# 2_viper_eagle_modern_matrix.net
KiCad netlist of a schematic drawn in Altium Designer
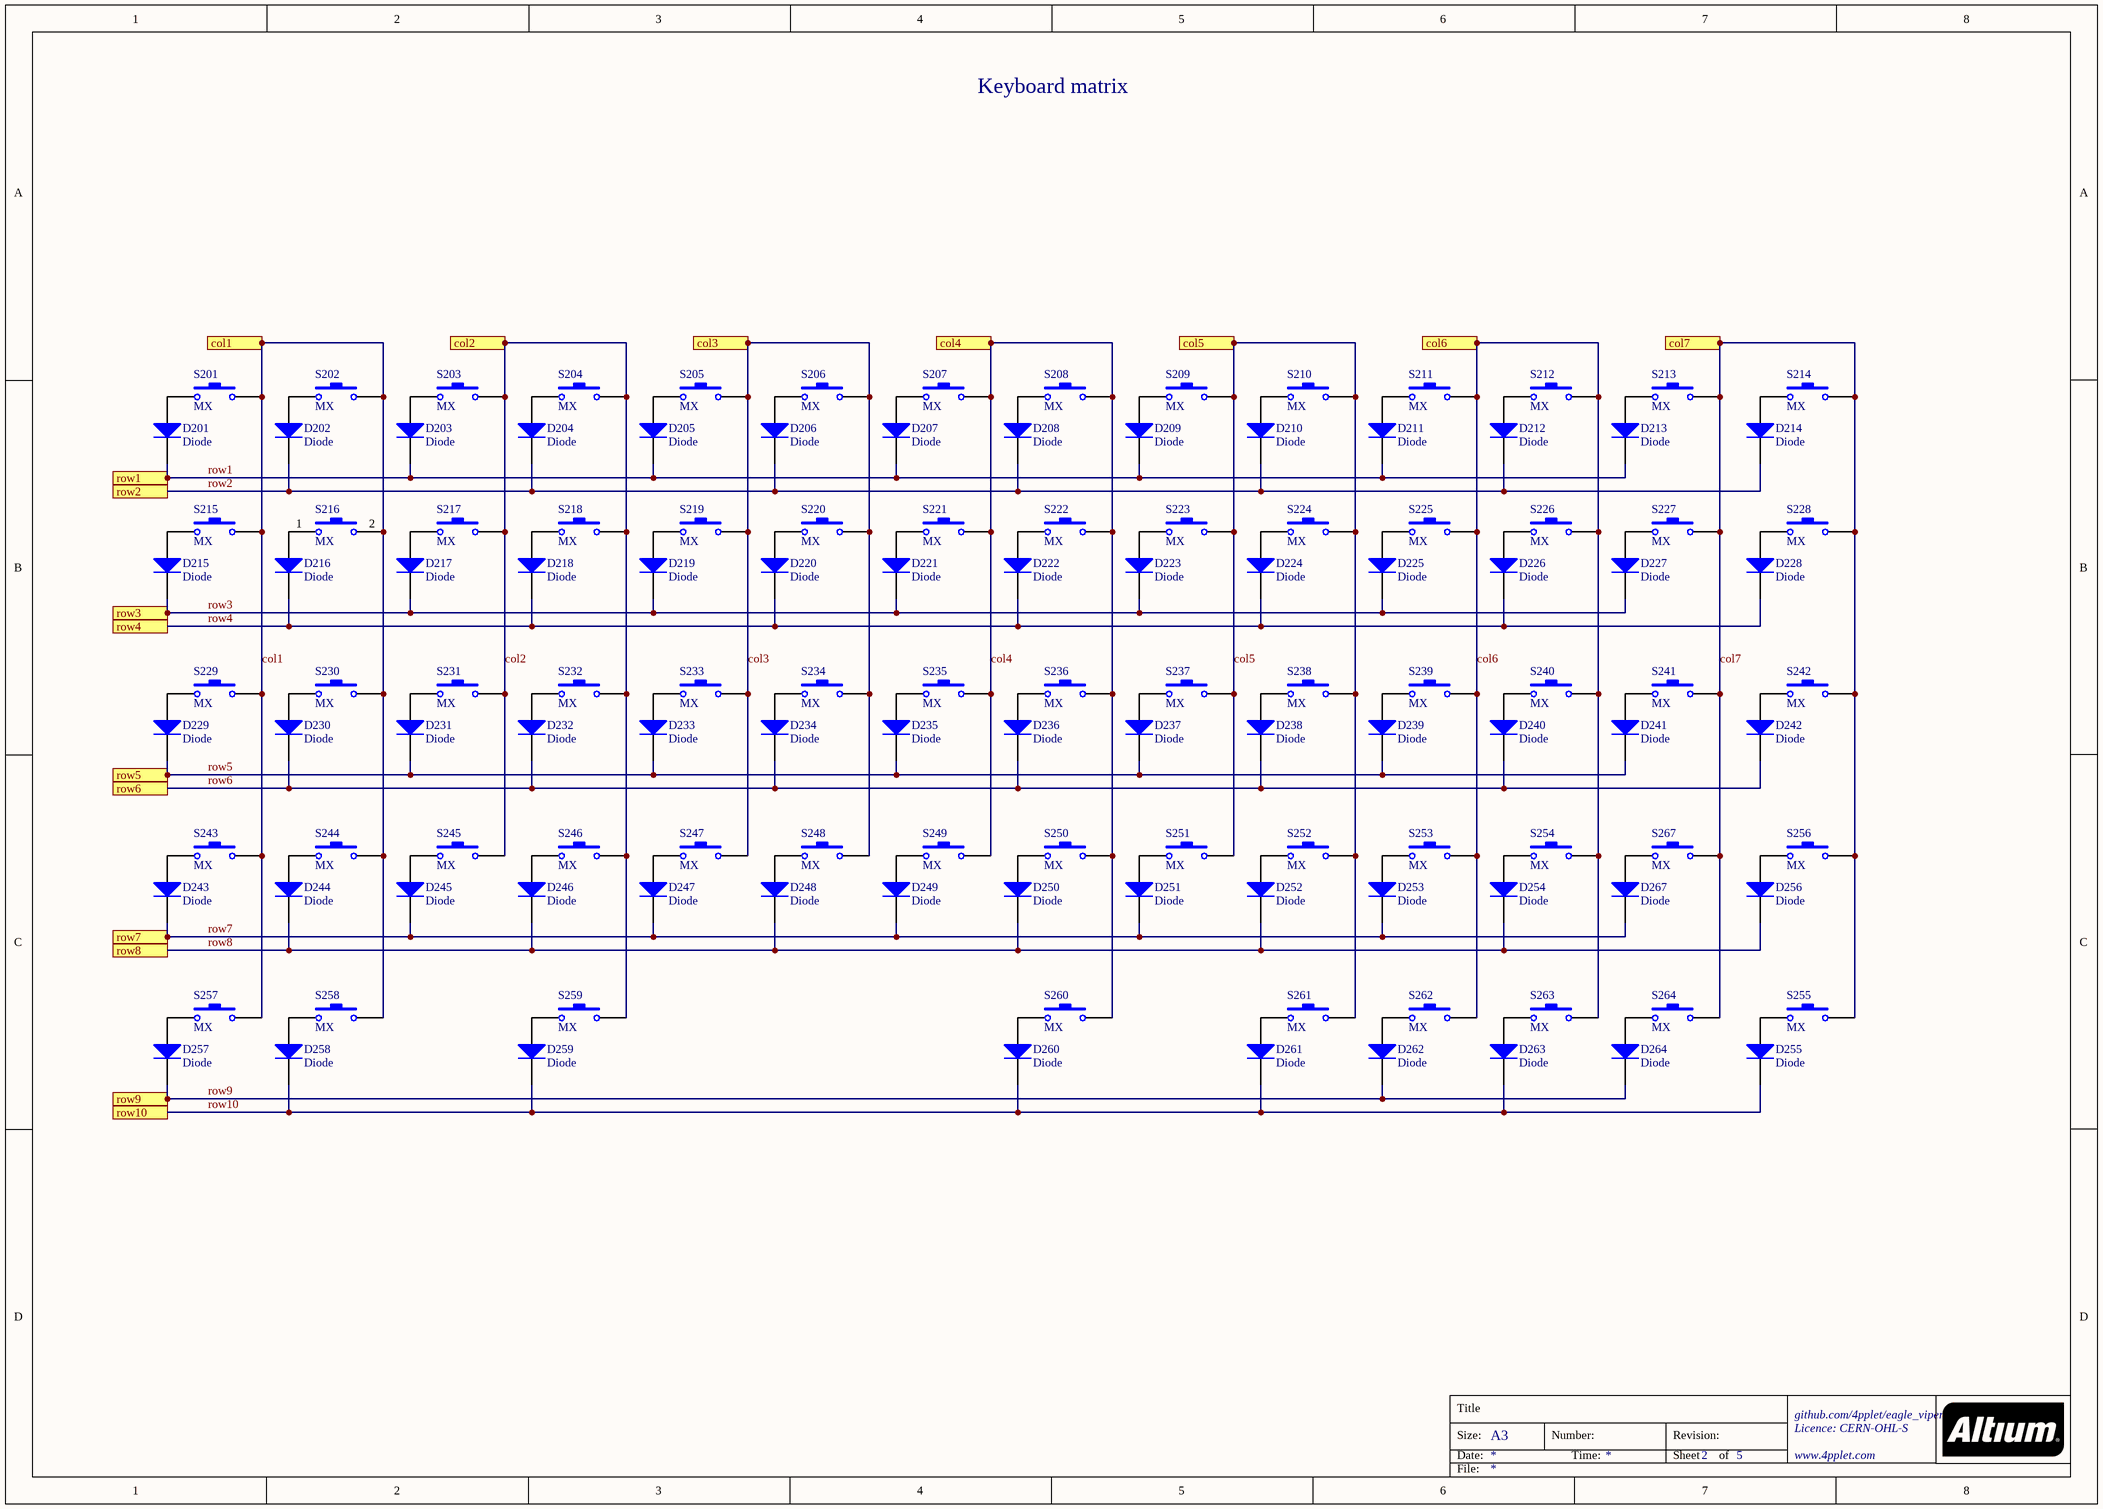
[diagram p0: 2_viper_eagle_modern_matrix.SchDoc]

(export (version "E")
  (design (tool "Eeschema 10.0.6"))
  (components
    (comp (ref "D201")
      (value "Diode")
      (footprint "SOD-123")
      (description "Default Diode")
      (fields (field (name "LCSC PART #") "C81598") (field (name "MRF.PART") "1N4148W"))
      (libsource (lib "Miscellaneous Devices") (part "Diode"))
    )
    (comp (ref "D202")
      (value "Diode")
      (footprint "SOD-123")
      (description "Default Diode")
      (fields (field (name "LCSC PART #") "C81598") (field (name "MRF.PART") "1N4148W"))
      (libsource (lib "Miscellaneous Devices") (part "Diode"))
    )
    (comp (ref "D203")
      (value "Diode")
      (footprint "SOD-123")
      (description "Default Diode")
      (fields (field (name "LCSC PART #") "C81598") (field (name "MRF.PART") "1N4148W"))
      (libsource (lib "Miscellaneous Devices") (part "Diode"))
    )
    (comp (ref "D204")
      (value "Diode")
      (footprint "SOD-123")
      (description "Default Diode")
      (fields (field (name "LCSC PART #") "C81598") (field (name "MRF.PART") "1N4148W"))
      (libsource (lib "Miscellaneous Devices") (part "Diode"))
    )
    (comp (ref "D205")
      (value "Diode")
      (footprint "SOD-123")
      (description "Default Diode")
      (fields (field (name "LCSC PART #") "C81598") (field (name "MRF.PART") "1N4148W"))
      (libsource (lib "Miscellaneous Devices") (part "Diode"))
    )
    (comp (ref "D206")
      (value "Diode")
      (footprint "SOD-123")
      (description "Default Diode")
      (fields (field (name "LCSC PART #") "C81598") (field (name "MRF.PART") "1N4148W"))
      (libsource (lib "Miscellaneous Devices") (part "Diode"))
    )
    (comp (ref "D207")
      (value "Diode")
      (footprint "SOD-123")
      (description "Default Diode")
      (fields (field (name "LCSC PART #") "C81598") (field (name "MRF.PART") "1N4148W"))
      (libsource (lib "Miscellaneous Devices") (part "Diode"))
    )
    (comp (ref "D208")
      (value "Diode")
      (footprint "SOD-123")
      (description "Default Diode")
      (fields (field (name "LCSC PART #") "C81598") (field (name "MRF.PART") "1N4148W"))
      (libsource (lib "Miscellaneous Devices") (part "Diode"))
    )
    (comp (ref "D209")
      (value "Diode")
      (footprint "SOD-123")
      (description "Default Diode")
      (fields (field (name "LCSC PART #") "C81598") (field (name "MRF.PART") "1N4148W"))
      (libsource (lib "Miscellaneous Devices") (part "Diode"))
    )
    (comp (ref "D210")
      (value "Diode")
      (footprint "SOD-123")
      (description "Default Diode")
      (fields (field (name "LCSC PART #") "C81598") (field (name "MRF.PART") "1N4148W"))
      (libsource (lib "Miscellaneous Devices") (part "Diode"))
    )
    (comp (ref "D211")
      (value "Diode")
      (footprint "SOD-123")
      (description "Default Diode")
      (fields (field (name "LCSC PART #") "C81598") (field (name "MRF.PART") "1N4148W"))
      (libsource (lib "Miscellaneous Devices") (part "Diode"))
    )
    (comp (ref "D212")
      (value "Diode")
      (footprint "SOD-123")
      (description "Default Diode")
      (fields (field (name "LCSC PART #") "C81598") (field (name "MRF.PART") "1N4148W"))
      (libsource (lib "Miscellaneous Devices") (part "Diode"))
    )
    (comp (ref "D213")
      (value "Diode")
      (footprint "SOD-123")
      (description "Default Diode")
      (fields (field (name "LCSC PART #") "C81598") (field (name "MRF.PART") "1N4148W"))
      (libsource (lib "Miscellaneous Devices") (part "Diode"))
    )
    (comp (ref "D214")
      (value "Diode")
      (footprint "SOD-123")
      (description "Default Diode")
      (fields (field (name "LCSC PART #") "C81598") (field (name "MRF.PART") "1N4148W"))
      (libsource (lib "Miscellaneous Devices") (part "Diode"))
    )
    (comp (ref "D215")
      (value "Diode")
      (footprint "SOD-123")
      (description "Default Diode")
      (fields (field (name "LCSC PART #") "C81598") (field (name "MRF.PART") "1N4148W"))
      (libsource (lib "Miscellaneous Devices") (part "Diode"))
    )
    (comp (ref "D216")
      (value "Diode")
      (footprint "SOD-123")
      (description "Default Diode")
      (fields (field (name "LCSC PART #") "C81598") (field (name "MRF.PART") "1N4148W"))
      (libsource (lib "Miscellaneous Devices") (part "Diode"))
    )
    (comp (ref "D217")
      (value "Diode")
      (footprint "SOD-123")
      (description "Default Diode")
      (fields (field (name "LCSC PART #") "C81598") (field (name "MRF.PART") "1N4148W"))
      (libsource (lib "Miscellaneous Devices") (part "Diode"))
    )
    (comp (ref "D218")
      (value "Diode")
      (footprint "SOD-123")
      (description "Default Diode")
      (fields (field (name "LCSC PART #") "C81598") (field (name "MRF.PART") "1N4148W"))
      (libsource (lib "Miscellaneous Devices") (part "Diode"))
    )
    (comp (ref "D219")
      (value "Diode")
      (footprint "SOD-123")
      (description "Default Diode")
      (fields (field (name "LCSC PART #") "C81598") (field (name "MRF.PART") "1N4148W"))
      (libsource (lib "Miscellaneous Devices") (part "Diode"))
    )
    (comp (ref "D220")
      (value "Diode")
      (footprint "SOD-123")
      (description "Default Diode")
      (fields (field (name "LCSC PART #") "C81598") (field (name "MRF.PART") "1N4148W"))
      (libsource (lib "Miscellaneous Devices") (part "Diode"))
    )
    (comp (ref "D221")
      (value "Diode")
      (footprint "SOD-123")
      (description "Default Diode")
      (fields (field (name "LCSC PART #") "C81598") (field (name "MRF.PART") "1N4148W"))
      (libsource (lib "Miscellaneous Devices") (part "Diode"))
    )
    (comp (ref "D222")
      (value "Diode")
      (footprint "SOD-123")
      (description "Default Diode")
      (fields (field (name "LCSC PART #") "C81598") (field (name "MRF.PART") "1N4148W"))
      (libsource (lib "Miscellaneous Devices") (part "Diode"))
    )
    (comp (ref "D223")
      (value "Diode")
      (footprint "SOD-123")
      (description "Default Diode")
      (fields (field (name "LCSC PART #") "C81598") (field (name "MRF.PART") "1N4148W"))
      (libsource (lib "Miscellaneous Devices") (part "Diode"))
    )
    (comp (ref "D224")
      (value "Diode")
      (footprint "SOD-123")
      (description "Default Diode")
      (fields (field (name "LCSC PART #") "C81598") (field (name "MRF.PART") "1N4148W"))
      (libsource (lib "Miscellaneous Devices") (part "Diode"))
    )
    (comp (ref "D225")
      (value "Diode")
      (footprint "SOD-123")
      (description "Default Diode")
      (fields (field (name "LCSC PART #") "C81598") (field (name "MRF.PART") "1N4148W"))
      (libsource (lib "Miscellaneous Devices") (part "Diode"))
    )
    (comp (ref "D226")
      (value "Diode")
      (footprint "SOD-123")
      (description "Default Diode")
      (fields (field (name "LCSC PART #") "C81598") (field (name "MRF.PART") "1N4148W"))
      (libsource (lib "Miscellaneous Devices") (part "Diode"))
    )
    (comp (ref "D227")
      (value "Diode")
      (footprint "SOD-123")
      (description "Default Diode")
      (fields (field (name "LCSC PART #") "C81598") (field (name "MRF.PART") "1N4148W"))
      (libsource (lib "Miscellaneous Devices") (part "Diode"))
    )
    (comp (ref "D228")
      (value "Diode")
      (footprint "SOD-123")
      (description "Default Diode")
      (fields (field (name "LCSC PART #") "C81598") (field (name "MRF.PART") "1N4148W"))
      (libsource (lib "Miscellaneous Devices") (part "Diode"))
    )
    (comp (ref "D229")
      (value "Diode")
      (footprint "SOD-123")
      (description "Default Diode")
      (fields (field (name "LCSC PART #") "C81598") (field (name "MRF.PART") "1N4148W"))
      (libsource (lib "Miscellaneous Devices") (part "Diode"))
    )
    (comp (ref "D230")
      (value "Diode")
      (footprint "SOD-123")
      (description "Default Diode")
      (fields (field (name "LCSC PART #") "C81598") (field (name "MRF.PART") "1N4148W"))
      (libsource (lib "Miscellaneous Devices") (part "Diode"))
    )
    (comp (ref "D231")
      (value "Diode")
      (footprint "SOD-123")
      (description "Default Diode")
      (fields (field (name "LCSC PART #") "C81598") (field (name "MRF.PART") "1N4148W"))
      (libsource (lib "Miscellaneous Devices") (part "Diode"))
    )
    (comp (ref "D232")
      (value "Diode")
      (footprint "SOD-123")
      (description "Default Diode")
      (fields (field (name "LCSC PART #") "C81598") (field (name "MRF.PART") "1N4148W"))
      (libsource (lib "Miscellaneous Devices") (part "Diode"))
    )
    (comp (ref "D233")
      (value "Diode")
      (footprint "SOD-123")
      (description "Default Diode")
      (fields (field (name "LCSC PART #") "C81598") (field (name "MRF.PART") "1N4148W"))
      (libsource (lib "Miscellaneous Devices") (part "Diode"))
    )
    (comp (ref "D234")
      (value "Diode")
      (footprint "SOD-123")
      (description "Default Diode")
      (fields (field (name "LCSC PART #") "C81598") (field (name "MRF.PART") "1N4148W"))
      (libsource (lib "Miscellaneous Devices") (part "Diode"))
    )
    (comp (ref "D235")
      (value "Diode")
      (footprint "SOD-123")
      (description "Default Diode")
      (fields (field (name "LCSC PART #") "C81598") (field (name "MRF.PART") "1N4148W"))
      (libsource (lib "Miscellaneous Devices") (part "Diode"))
    )
    (comp (ref "D236")
      (value "Diode")
      (footprint "SOD-123")
      (description "Default Diode")
      (fields (field (name "LCSC PART #") "C81598") (field (name "MRF.PART") "1N4148W"))
      (libsource (lib "Miscellaneous Devices") (part "Diode"))
    )
    (comp (ref "D237")
      (value "Diode")
      (footprint "SOD-123")
      (description "Default Diode")
      (fields (field (name "LCSC PART #") "C81598") (field (name "MRF.PART") "1N4148W"))
      (libsource (lib "Miscellaneous Devices") (part "Diode"))
    )
    (comp (ref "D238")
      (value "Diode")
      (footprint "SOD-123")
      (description "Default Diode")
      (fields (field (name "LCSC PART #") "C81598") (field (name "MRF.PART") "1N4148W"))
      (libsource (lib "Miscellaneous Devices") (part "Diode"))
    )
    (comp (ref "D239")
      (value "Diode")
      (footprint "SOD-123")
      (description "Default Diode")
      (fields (field (name "LCSC PART #") "C81598") (field (name "MRF.PART") "1N4148W"))
      (libsource (lib "Miscellaneous Devices") (part "Diode"))
    )
    (comp (ref "D240")
      (value "Diode")
      (footprint "SOD-123")
      (description "Default Diode")
      (fields (field (name "LCSC PART #") "C81598") (field (name "MRF.PART") "1N4148W"))
      (libsource (lib "Miscellaneous Devices") (part "Diode"))
    )
    (comp (ref "D241")
      (value "Diode")
      (footprint "SOD-123")
      (description "Default Diode")
      (fields (field (name "LCSC PART #") "C81598") (field (name "MRF.PART") "1N4148W"))
      (libsource (lib "Miscellaneous Devices") (part "Diode"))
    )
    (comp (ref "D242")
      (value "Diode")
      (footprint "SOD-123")
      (description "Default Diode")
      (fields (field (name "LCSC PART #") "C81598") (field (name "MRF.PART") "1N4148W"))
      (libsource (lib "Miscellaneous Devices") (part "Diode"))
    )
    (comp (ref "D243")
      (value "Diode")
      (footprint "SOD-123")
      (description "Default Diode")
      (fields (field (name "LCSC PART #") "C81598") (field (name "MRF.PART") "1N4148W"))
      (libsource (lib "Miscellaneous Devices") (part "Diode"))
    )
    (comp (ref "D244")
      (value "Diode")
      (footprint "SOD-123")
      (description "Default Diode")
      (fields (field (name "LCSC PART #") "C81598") (field (name "MRF.PART") "1N4148W"))
      (libsource (lib "Miscellaneous Devices") (part "Diode"))
    )
    (comp (ref "D245")
      (value "Diode")
      (footprint "SOD-123")
      (description "Default Diode")
      (fields (field (name "LCSC PART #") "C81598") (field (name "MRF.PART") "1N4148W"))
      (libsource (lib "Miscellaneous Devices") (part "Diode"))
    )
    (comp (ref "D246")
      (value "Diode")
      (footprint "SOD-123")
      (description "Default Diode")
      (fields (field (name "LCSC PART #") "C81598") (field (name "MRF.PART") "1N4148W"))
      (libsource (lib "Miscellaneous Devices") (part "Diode"))
    )
    (comp (ref "D247")
      (value "Diode")
      (footprint "SOD-123")
      (description "Default Diode")
      (fields (field (name "LCSC PART #") "C81598") (field (name "MRF.PART") "1N4148W"))
      (libsource (lib "Miscellaneous Devices") (part "Diode"))
    )
    (comp (ref "D248")
      (value "Diode")
      (footprint "SOD-123")
      (description "Default Diode")
      (fields (field (name "LCSC PART #") "C81598") (field (name "MRF.PART") "1N4148W"))
      (libsource (lib "Miscellaneous Devices") (part "Diode"))
    )
    (comp (ref "D249")
      (value "Diode")
      (footprint "SOD-123")
      (description "Default Diode")
      (fields (field (name "LCSC PART #") "C81598") (field (name "MRF.PART") "1N4148W"))
      (libsource (lib "Miscellaneous Devices") (part "Diode"))
    )
    (comp (ref "D250")
      (value "Diode")
      (footprint "SOD-123")
      (description "Default Diode")
      (fields (field (name "LCSC PART #") "C81598") (field (name "MRF.PART") "1N4148W"))
      (libsource (lib "Miscellaneous Devices") (part "Diode"))
    )
    (comp (ref "D251")
      (value "Diode")
      (footprint "SOD-123")
      (description "Default Diode")
      (fields (field (name "LCSC PART #") "C81598") (field (name "MRF.PART") "1N4148W"))
      (libsource (lib "Miscellaneous Devices") (part "Diode"))
    )
    (comp (ref "D252")
      (value "Diode")
      (footprint "SOD-123")
      (description "Default Diode")
      (fields (field (name "LCSC PART #") "C81598") (field (name "MRF.PART") "1N4148W"))
      (libsource (lib "Miscellaneous Devices") (part "Diode"))
    )
    (comp (ref "D253")
      (value "Diode")
      (footprint "SOD-123")
      (description "Default Diode")
      (fields (field (name "LCSC PART #") "C81598") (field (name "MRF.PART") "1N4148W"))
      (libsource (lib "Miscellaneous Devices") (part "Diode"))
    )
    (comp (ref "D254")
      (value "Diode")
      (footprint "SOD-123")
      (description "Default Diode")
      (fields (field (name "LCSC PART #") "C81598") (field (name "MRF.PART") "1N4148W"))
      (libsource (lib "Miscellaneous Devices") (part "Diode"))
    )
    (comp (ref "D255")
      (value "Diode")
      (footprint "SOD-123")
      (description "Default Diode")
      (fields (field (name "LCSC PART #") "C81598") (field (name "MRF.PART") "1N4148W"))
      (libsource (lib "Miscellaneous Devices") (part "Diode"))
    )
    (comp (ref "D256")
      (value "Diode")
      (footprint "SOD-123")
      (description "Default Diode")
      (fields (field (name "LCSC PART #") "C81598") (field (name "MRF.PART") "1N4148W"))
      (libsource (lib "Miscellaneous Devices") (part "Diode"))
    )
    (comp (ref "D257")
      (value "Diode")
      (footprint "SOD-123")
      (description "Default Diode")
      (fields (field (name "LCSC PART #") "C81598") (field (name "MRF.PART") "1N4148W"))
      (libsource (lib "Miscellaneous Devices") (part "Diode"))
    )
    (comp (ref "D258")
      (value "Diode")
      (footprint "SOD-123")
      (description "Default Diode")
      (fields (field (name "LCSC PART #") "C81598") (field (name "MRF.PART") "1N4148W"))
      (libsource (lib "Miscellaneous Devices") (part "Diode"))
    )
    (comp (ref "D259")
      (value "Diode")
      (footprint "SOD-123")
      (description "Default Diode")
      (fields (field (name "LCSC PART #") "C81598") (field (name "MRF.PART") "1N4148W"))
      (libsource (lib "Miscellaneous Devices") (part "Diode"))
    )
    (comp (ref "D260")
      (value "Diode")
      (footprint "SOD-123")
      (description "Default Diode")
      (fields (field (name "LCSC PART #") "C81598") (field (name "MRF.PART") "1N4148W"))
      (libsource (lib "Miscellaneous Devices") (part "Diode"))
    )
    (comp (ref "D261")
      (value "Diode")
      (footprint "SOD-123")
      (description "Default Diode")
      (fields (field (name "LCSC PART #") "C81598") (field (name "MRF.PART") "1N4148W"))
      (libsource (lib "Miscellaneous Devices") (part "Diode"))
    )
    (comp (ref "D262")
      (value "Diode")
      (footprint "SOD-123")
      (description "Default Diode")
      (fields (field (name "LCSC PART #") "C81598") (field (name "MRF.PART") "1N4148W"))
      (libsource (lib "Miscellaneous Devices") (part "Diode"))
    )
    (comp (ref "D263")
      (value "Diode")
      (footprint "SOD-123")
      (description "Default Diode")
      (fields (field (name "LCSC PART #") "C81598") (field (name "MRF.PART") "1N4148W"))
      (libsource (lib "Miscellaneous Devices") (part "Diode"))
    )
    (comp (ref "D264")
      (value "Diode")
      (footprint "SOD-123")
      (description "Default Diode")
      (fields (field (name "LCSC PART #") "C81598") (field (name "MRF.PART") "1N4148W"))
      (libsource (lib "Miscellaneous Devices") (part "Diode"))
    )
    (comp (ref "D267")
      (value "Diode")
      (footprint "SOD-123")
      (description "Default Diode")
      (fields (field (name "LCSC PART #") "C81598") (field (name "MRF.PART") "1N4148W"))
      (libsource (lib "Miscellaneous Devices") (part "Diode"))
    )
    (comp (ref "S201")
      (value "MX")
      (footprint "MX-switch - switched pol")
      (description "Switch")
      (libsource (lib "Miscellaneous Devices") (part "SW-PB"))
    )
    (comp (ref "S202")
      (value "MX")
      (footprint "MX-switch - switched pol - connector")
      (description "Switch")
      (libsource (lib "Miscellaneous Devices") (part "SW-PB"))
    )
    (comp (ref "S203")
      (value "MX")
      (footprint "MX-switch - switched pol")
      (description "Switch")
      (libsource (lib "Miscellaneous Devices") (part "SW-PB"))
    )
    (comp (ref "S204")
      (value "MX")
      (footprint "MX-switch - switched pol")
      (description "Switch")
      (libsource (lib "Miscellaneous Devices") (part "SW-PB"))
    )
    (comp (ref "S205")
      (value "MX")
      (footprint "MX-switch - switched pol")
      (description "Switch")
      (libsource (lib "Miscellaneous Devices") (part "SW-PB"))
    )
    (comp (ref "S206")
      (value "MX")
      (footprint "MX-switch - switched pol")
      (description "Switch")
      (libsource (lib "Miscellaneous Devices") (part "SW-PB"))
    )
    (comp (ref "S207")
      (value "MX")
      (footprint "MX-switch")
      (description "Switch")
      (libsource (lib "Miscellaneous Devices") (part "SW-PB"))
    )
    (comp (ref "S208")
      (value "MX")
      (footprint "MX-switch - switched pol")
      (description "Switch")
      (libsource (lib "Miscellaneous Devices") (part "SW-PB"))
    )
    (comp (ref "S209")
      (value "MX")
      (footprint "MX-switch - switched pol")
      (description "Switch")
      (libsource (lib "Miscellaneous Devices") (part "SW-PB"))
    )
    (comp (ref "S210")
      (value "MX")
      (footprint "MX-switch - switched pol")
      (description "Switch")
      (libsource (lib "Miscellaneous Devices") (part "SW-PB"))
    )
    (comp (ref "S211")
      (value "MX")
      (footprint "MX-switch - switched pol")
      (description "Switch")
      (libsource (lib "Miscellaneous Devices") (part "SW-PB"))
    )
    (comp (ref "S212")
      (value "MX")
      (footprint "MX-switch - switched pol")
      (description "Switch")
      (libsource (lib "Miscellaneous Devices") (part "SW-PB"))
    )
    (comp (ref "S213")
      (value "MX")
      (footprint "MX-switch - switched pol")
      (description "Switch")
      (libsource (lib "Miscellaneous Devices") (part "SW-PB"))
    )
    (comp (ref "S214")
      (value "MX")
      (footprint "MX-switch")
      (description "Switch")
      (libsource (lib "Miscellaneous Devices") (part "SW-PB"))
    )
    (comp (ref "S215")
      (value "MX")
      (footprint "MX-switch - 1.5U")
      (description "TAB")
      (libsource (lib "Miscellaneous Devices") (part "SW-PB"))
    )
    (comp (ref "S216")
      (value "MX")
      (footprint "MX-switch - switched pol")
      (description "Switch")
      (libsource (lib "") (part "SW-PB_1"))
    )
    (comp (ref "S217")
      (value "MX")
      (footprint "MX-switch - switched pol")
      (description "Switch")
      (libsource (lib "Miscellaneous Devices") (part "SW-PB"))
    )
    (comp (ref "S218")
      (value "MX")
      (footprint "MX-switch - switched pol")
      (description "Switch")
      (libsource (lib "Miscellaneous Devices") (part "SW-PB"))
    )
    (comp (ref "S219")
      (value "MX")
      (footprint "MX-switch - switched pol")
      (description "Switch")
      (libsource (lib "Miscellaneous Devices") (part "SW-PB"))
    )
    (comp (ref "S220")
      (value "MX")
      (footprint "MX-switch")
      (description "Switch")
      (libsource (lib "Miscellaneous Devices") (part "SW-PB"))
    )
    (comp (ref "S221")
      (value "MX")
      (footprint "MX-switch - switched pol")
      (description "Switch")
      (libsource (lib "Miscellaneous Devices") (part "SW-PB"))
    )
    (comp (ref "S222")
      (value "MX")
      (footprint "MX-switch - switched pol")
      (description "Switch")
      (libsource (lib "Miscellaneous Devices") (part "SW-PB"))
    )
    (comp (ref "S223")
      (value "MX")
      (footprint "MX-switch - switched pol")
      (description "Switch")
      (libsource (lib "Miscellaneous Devices") (part "SW-PB"))
    )
    (comp (ref "S224")
      (value "MX")
      (footprint "MX-switch - switched pol")
      (description "Switch")
      (libsource (lib "Miscellaneous Devices") (part "SW-PB"))
    )
    (comp (ref "S225")
      (value "MX")
      (footprint "MX-switch - switched pol")
      (description "Switch")
      (libsource (lib "Miscellaneous Devices") (part "SW-PB"))
    )
    (comp (ref "S226")
      (value "MX")
      (footprint "MX-switch")
      (description "Switch")
      (libsource (lib "Miscellaneous Devices") (part "SW-PB"))
    )
    (comp (ref "S227")
      (value "MX")
      (footprint "MX-switch - switched pol")
      (description "Switch")
      (libsource (lib "Miscellaneous Devices") (part "SW-PB"))
    )
    (comp (ref "S228")
      (value "MX")
      (footprint "MX-switch - backspace")
      (description "Switch")
      (libsource (lib "Miscellaneous Devices") (part "SW-PB"))
    )
    (comp (ref "S229")
      (value "MX")
      (footprint "MX-switch - CAPS")
      (description "Switch")
      (libsource (lib "Miscellaneous Devices") (part "SW-PB"))
    )
    (comp (ref "S230")
      (value "MX")
      (footprint "MX-switch - switched pol")
      (description "Switch")
      (libsource (lib "Miscellaneous Devices") (part "SW-PB"))
    )
    (comp (ref "S231")
      (value "MX")
      (footprint "MX-switch - switched pol")
      (description "Switch")
      (libsource (lib "Miscellaneous Devices") (part "SW-PB"))
    )
    (comp (ref "S232")
      (value "MX")
      (footprint "MX-switch - switched pol")
      (description "Switch")
      (libsource (lib "Miscellaneous Devices") (part "SW-PB"))
    )
    (comp (ref "S233")
      (value "MX")
      (footprint "MX-switch - switched pol")
      (description "Switch")
      (libsource (lib "Miscellaneous Devices") (part "SW-PB"))
    )
    (comp (ref "S234")
      (value "MX")
      (footprint "MX-switch - switched pol")
      (description "Switch")
      (libsource (lib "Miscellaneous Devices") (part "SW-PB"))
    )
    (comp (ref "S235")
      (value "MX")
      (footprint "MX-switch - switched pol")
      (description "Switch")
      (libsource (lib "Miscellaneous Devices") (part "SW-PB"))
    )
    (comp (ref "S236")
      (value "MX")
      (footprint "MX-switch - switched pol")
      (description "Switch")
      (libsource (lib "Miscellaneous Devices") (part "SW-PB"))
    )
    (comp (ref "S237")
      (value "MX")
      (footprint "MX-switch - switched pol")
      (description "Switch")
      (libsource (lib "Miscellaneous Devices") (part "SW-PB"))
    )
    (comp (ref "S238")
      (value "MX")
      (footprint "MX-switch - switched pol")
      (description "Switch")
      (libsource (lib "Miscellaneous Devices") (part "SW-PB"))
    )
    (comp (ref "S239")
      (value "MX")
      (footprint "MX-switch")
      (description "Switch")
      (libsource (lib "Miscellaneous Devices") (part "SW-PB"))
    )
    (comp (ref "S240")
      (value "MX")
      (footprint "MX-switch - switched pol")
      (description "Switch")
      (libsource (lib "Miscellaneous Devices") (part "SW-PB"))
    )
    (comp (ref "S241")
      (value "MX")
      (footprint "MX-switch")
      (description "Switch")
      (libsource (lib "Miscellaneous Devices") (part "SW-PB"))
    )
    (comp (ref "S242")
      (value "MX")
      (footprint "MX-switch - 1.5U")
      (description "Switch")
      (libsource (lib "Miscellaneous Devices") (part "SW-PB"))
    )
    (comp (ref "S243")
      (value "MX")
      (footprint "MX-switch - Left shift")
      (description "Switch")
      (libsource (lib "Miscellaneous Devices") (part "SW-PB"))
    )
    (comp (ref "S244")
      (value "MX")
      (footprint "MX-switch")
      (description "Switch")
      (libsource (lib "Miscellaneous Devices") (part "SW-PB"))
    )
    (comp (ref "S245")
      (value "MX")
      (footprint "MX-switch - switched pol")
      (description "Switch")
      (libsource (lib "Miscellaneous Devices") (part "SW-PB"))
    )
    (comp (ref "S246")
      (value "MX")
      (footprint "MX-switch - switched pol")
      (description "Switch")
      (libsource (lib "Miscellaneous Devices") (part "SW-PB"))
    )
    (comp (ref "S247")
      (value "MX")
      (footprint "MX-switch - switched pol")
      (description "Switch")
      (libsource (lib "Miscellaneous Devices") (part "SW-PB"))
    )
    (comp (ref "S248")
      (value "MX")
      (footprint "MX-switch - switched pol")
      (description "Switch")
      (libsource (lib "Miscellaneous Devices") (part "SW-PB"))
    )
    (comp (ref "S249")
      (value "MX")
      (footprint "MX-switch - switched pol")
      (description "Switch")
      (libsource (lib "Miscellaneous Devices") (part "SW-PB"))
    )
    (comp (ref "S250")
      (value "MX")
      (footprint "MX-switch - switched pol")
      (description "Switch")
      (libsource (lib "Miscellaneous Devices") (part "SW-PB"))
    )
    (comp (ref "S251")
      (value "MX")
      (footprint "MX-switch - switched pol")
      (description "Switch")
      (libsource (lib "Miscellaneous Devices") (part "SW-PB"))
    )
    (comp (ref "S252")
      (value "MX")
      (footprint "MX-switch - switched pol")
      (description "Switch")
      (libsource (lib "Miscellaneous Devices") (part "SW-PB"))
    )
    (comp (ref "S253")
      (value "MX")
      (footprint "MX-switch - switched pol")
      (description "Switch")
      (libsource (lib "Miscellaneous Devices") (part "SW-PB"))
    )
    (comp (ref "S254")
      (value "MX")
      (footprint "MX-switch - switched pol")
      (description "Switch")
      (libsource (lib "Miscellaneous Devices") (part "SW-PB"))
    )
    (comp (ref "S255")
      (value "MX")
      (footprint "MX-switch")
      (description "Switch")
      (libsource (lib "Miscellaneous Devices") (part "SW-PB"))
    )
    (comp (ref "S256")
      (value "MX")
      (footprint "MX-switch - Enter - rotated ISO")
      (description "Switch")
      (libsource (lib "Miscellaneous Devices") (part "SW-PB"))
    )
    (comp (ref "S257")
      (value "MX")
      (footprint "MX-switch - 1.5u MOD-L")
      (description "Switch")
      (libsource (lib "Miscellaneous Devices") (part "SW-PB"))
    )
    (comp (ref "S258")
      (value "MX")
      (footprint "MX-switch - 1u MOD-L")
      (description "Switch")
      (libsource (lib "Miscellaneous Devices") (part "SW-PB"))
    )
    (comp (ref "S259")
      (value "MX")
      (footprint "MX-switch - 1.5u MOD-L")
      (description "Switch")
      (libsource (lib "Miscellaneous Devices") (part "SW-PB"))
    )
    (comp (ref "S260")
      (value "MX")
      (footprint "MX-switch - Space_V2")
      (description "Switch")
      (libsource (lib "Miscellaneous Devices") (part "SW-PB"))
    )
    (comp (ref "S261")
      (value "MX")
      (footprint "MX-switch")
      (description "Switch")
      (libsource (lib "Miscellaneous Devices") (part "SW-PB"))
    )
    (comp (ref "S262")
      (value "MX")
      (footprint "MX-switch - 1.5u MOD-R")
      (description "Switch")
      (libsource (lib "Miscellaneous Devices") (part "SW-PB"))
    )
    (comp (ref "S263")
      (value "MX")
      (footprint "MX-switch - 1u MOD-R")
      (description "Switch")
      (libsource (lib "Miscellaneous Devices") (part "SW-PB"))
    )
    (comp (ref "S264")
      (value "MX")
      (footprint "MX-switch - 1.5u MOD-R")
      (description "Switch")
      (libsource (lib "Miscellaneous Devices") (part "SW-PB"))
    )
    (comp (ref "S267")
      (value "MX")
      (footprint "MX-switch - right shift - rotated stab")
      (description "Switch")
      (libsource (lib "Miscellaneous Devices") (part "SW-PB"))
    )
  )
  (nets
    (net (code "1") (name "/col1") (class "Default")
      (node (ref "S201") (pin "2") (pinfunction "2_2") (pintype "passive"))
      (node (ref "S202") (pin "2") (pinfunction "2_2") (pintype "passive"))
      (node (ref "S215") (pin "1") (pinfunction "1_1") (pintype "passive"))
      (node (ref "S216") (pin "2") (pinfunction "2_2") (pintype "passive"))
      (node (ref "S229") (pin "2") (pinfunction "2_2") (pintype "passive"))
      (node (ref "S230") (pin "2") (pinfunction "2_2") (pintype "passive"))
      (node (ref "S243") (pin "2") (pinfunction "2_2") (pintype "passive"))
      (node (ref "S244") (pin "2") (pinfunction "2_2") (pintype "passive"))
      (node (ref "S257") (pin "1") (pinfunction "1_1") (pintype "passive"))
      (node (ref "S258") (pin "2") (pinfunction "2_2") (pintype "passive"))
    )
    (net (code "2") (name "/col2") (class "Default")
      (node (ref "S203") (pin "2") (pinfunction "2_2") (pintype "passive"))
      (node (ref "S204") (pin "2") (pinfunction "2_2") (pintype "passive"))
      (node (ref "S217") (pin "2") (pinfunction "2_2") (pintype "passive"))
      (node (ref "S218") (pin "2") (pinfunction "2_2") (pintype "passive"))
      (node (ref "S231") (pin "2") (pinfunction "2_2") (pintype "passive"))
      (node (ref "S232") (pin "2") (pinfunction "2_2") (pintype "passive"))
      (node (ref "S245") (pin "2") (pinfunction "2_2") (pintype "passive"))
      (node (ref "S246") (pin "2") (pinfunction "2_2") (pintype "passive"))
      (node (ref "S259") (pin "1") (pinfunction "1_1") (pintype "passive"))
    )
    (net (code "3") (name "/col3") (class "Default")
      (node (ref "S205") (pin "2") (pinfunction "2_2") (pintype "passive"))
      (node (ref "S206") (pin "2") (pinfunction "2_2") (pintype "passive"))
      (node (ref "S219") (pin "2") (pinfunction "2_2") (pintype "passive"))
      (node (ref "S220") (pin "2") (pinfunction "2_2") (pintype "passive"))
      (node (ref "S233") (pin "2") (pinfunction "2_2") (pintype "passive"))
      (node (ref "S234") (pin "2") (pinfunction "2_2") (pintype "passive"))
      (node (ref "S247") (pin "2") (pinfunction "2_2") (pintype "passive"))
      (node (ref "S248") (pin "2") (pinfunction "2_2") (pintype "passive"))
    )
    (net (code "4") (name "/col4") (class "Default")
      (node (ref "S207") (pin "2") (pinfunction "2_2") (pintype "passive"))
      (node (ref "S208") (pin "2") (pinfunction "2_2") (pintype "passive"))
      (node (ref "S221") (pin "2") (pinfunction "2_2") (pintype "passive"))
      (node (ref "S222") (pin "2") (pinfunction "2_2") (pintype "passive"))
      (node (ref "S235") (pin "2") (pinfunction "2_2") (pintype "passive"))
      (node (ref "S236") (pin "2") (pinfunction "2_2") (pintype "passive"))
      (node (ref "S249") (pin "2") (pinfunction "2_2") (pintype "passive"))
      (node (ref "S250") (pin "2") (pinfunction "2_2") (pintype "passive"))
      (node (ref "S260") (pin "1") (pinfunction "1_1") (pintype "passive"))
    )
    (net (code "5") (name "/col5") (class "Default")
      (node (ref "S209") (pin "2") (pinfunction "2_2") (pintype "passive"))
      (node (ref "S210") (pin "2") (pinfunction "2_2") (pintype "passive"))
      (node (ref "S223") (pin "2") (pinfunction "2_2") (pintype "passive"))
      (node (ref "S224") (pin "2") (pinfunction "2_2") (pintype "passive"))
      (node (ref "S237") (pin "2") (pinfunction "2_2") (pintype "passive"))
      (node (ref "S238") (pin "2") (pinfunction "2_2") (pintype "passive"))
      (node (ref "S251") (pin "2") (pinfunction "2_2") (pintype "passive"))
      (node (ref "S252") (pin "2") (pinfunction "2_2") (pintype "passive"))
      (node (ref "S261") (pin "2") (pinfunction "2_2") (pintype "passive"))
    )
    (net (code "6") (name "/col6") (class "Default")
      (node (ref "S211") (pin "2") (pinfunction "2_2") (pintype "passive"))
      (node (ref "S212") (pin "2") (pinfunction "2_2") (pintype "passive"))
      (node (ref "S225") (pin "2") (pinfunction "2_2") (pintype "passive"))
      (node (ref "S226") (pin "2") (pinfunction "2_2") (pintype "passive"))
      (node (ref "S239") (pin "2") (pinfunction "2_2") (pintype "passive"))
      (node (ref "S240") (pin "2") (pinfunction "2_2") (pintype "passive"))
      (node (ref "S253") (pin "2") (pinfunction "2_2") (pintype "passive"))
      (node (ref "S254") (pin "2") (pinfunction "2_2") (pintype "passive"))
      (node (ref "S262") (pin "1") (pinfunction "1_1") (pintype "passive"))
      (node (ref "S263") (pin "1") (pinfunction "1_1") (pintype "passive"))
    )
    (net (code "7") (name "/col7") (class "Default")
      (node (ref "S213") (pin "2") (pinfunction "2_2") (pintype "passive"))
      (node (ref "S214") (pin "2") (pinfunction "2_2") (pintype "passive"))
      (node (ref "S227") (pin "2") (pinfunction "2_2") (pintype "passive"))
      (node (ref "S228") (pin "1") (pinfunction "1_1") (pintype "passive"))
      (node (ref "S241") (pin "2") (pinfunction "2_2") (pintype "passive"))
      (node (ref "S242") (pin "2") (pinfunction "2_2") (pintype "passive"))
      (node (ref "S255") (pin "2") (pinfunction "2_2") (pintype "passive"))
      (node (ref "S256") (pin "2") (pinfunction "2_2") (pintype "passive"))
      (node (ref "S264") (pin "2") (pinfunction "2_2") (pintype "passive"))
      (node (ref "S267") (pin "2") (pinfunction "2_2") (pintype "passive"))
    )
    (net (code "8") (name "/row1") (class "Default")
      (node (ref "D201") (pin "2") (pinfunction "K_2") (pintype "passive"))
      (node (ref "D203") (pin "2") (pinfunction "K_2") (pintype "passive"))
      (node (ref "D205") (pin "2") (pinfunction "K_2") (pintype "passive"))
      (node (ref "D207") (pin "2") (pinfunction "K_2") (pintype "passive"))
      (node (ref "D209") (pin "2") (pinfunction "K_2") (pintype "passive"))
      (node (ref "D211") (pin "2") (pinfunction "K_2") (pintype "passive"))
      (node (ref "D213") (pin "2") (pinfunction "K_2") (pintype "passive"))
    )
    (net (code "9") (name "/row2") (class "Default")
      (node (ref "D202") (pin "2") (pinfunction "K_2") (pintype "passive"))
      (node (ref "D204") (pin "2") (pinfunction "K_2") (pintype "passive"))
      (node (ref "D206") (pin "2") (pinfunction "K_2") (pintype "passive"))
      (node (ref "D208") (pin "2") (pinfunction "K_2") (pintype "passive"))
      (node (ref "D210") (pin "2") (pinfunction "K_2") (pintype "passive"))
      (node (ref "D212") (pin "2") (pinfunction "K_2") (pintype "passive"))
      (node (ref "D214") (pin "2") (pinfunction "K_2") (pintype "passive"))
    )
    (net (code "10") (name "/row3") (class "Default")
      (node (ref "D215") (pin "2") (pinfunction "K_2") (pintype "passive"))
      (node (ref "D217") (pin "2") (pinfunction "K_2") (pintype "passive"))
      (node (ref "D219") (pin "2") (pinfunction "K_2") (pintype "passive"))
      (node (ref "D221") (pin "2") (pinfunction "K_2") (pintype "passive"))
      (node (ref "D223") (pin "2") (pinfunction "K_2") (pintype "passive"))
      (node (ref "D225") (pin "2") (pinfunction "K_2") (pintype "passive"))
      (node (ref "D227") (pin "2") (pinfunction "K_2") (pintype "passive"))
    )
    (net (code "11") (name "/row4") (class "Default")
      (node (ref "D216") (pin "2") (pinfunction "K_2") (pintype "passive"))
      (node (ref "D218") (pin "2") (pinfunction "K_2") (pintype "passive"))
      (node (ref "D220") (pin "2") (pinfunction "K_2") (pintype "passive"))
      (node (ref "D222") (pin "2") (pinfunction "K_2") (pintype "passive"))
      (node (ref "D224") (pin "2") (pinfunction "K_2") (pintype "passive"))
      (node (ref "D226") (pin "2") (pinfunction "K_2") (pintype "passive"))
      (node (ref "D228") (pin "2") (pinfunction "K_2") (pintype "passive"))
    )
    (net (code "12") (name "/row5") (class "Default")
      (node (ref "D229") (pin "2") (pinfunction "K_2") (pintype "passive"))
      (node (ref "D231") (pin "2") (pinfunction "K_2") (pintype "passive"))
      (node (ref "D233") (pin "2") (pinfunction "K_2") (pintype "passive"))
      (node (ref "D235") (pin "2") (pinfunction "K_2") (pintype "passive"))
      (node (ref "D237") (pin "2") (pinfunction "K_2") (pintype "passive"))
      (node (ref "D239") (pin "2") (pinfunction "K_2") (pintype "passive"))
      (node (ref "D241") (pin "2") (pinfunction "K_2") (pintype "passive"))
    )
    (net (code "13") (name "/row6") (class "Default")
      (node (ref "D230") (pin "2") (pinfunction "K_2") (pintype "passive"))
      (node (ref "D232") (pin "2") (pinfunction "K_2") (pintype "passive"))
      (node (ref "D234") (pin "2") (pinfunction "K_2") (pintype "passive"))
      (node (ref "D236") (pin "2") (pinfunction "K_2") (pintype "passive"))
      (node (ref "D238") (pin "2") (pinfunction "K_2") (pintype "passive"))
      (node (ref "D240") (pin "2") (pinfunction "K_2") (pintype "passive"))
      (node (ref "D242") (pin "2") (pinfunction "K_2") (pintype "passive"))
    )
    (net (code "14") (name "/row7") (class "Default")
      (node (ref "D243") (pin "2") (pinfunction "K_2") (pintype "passive"))
      (node (ref "D245") (pin "2") (pinfunction "K_2") (pintype "passive"))
      (node (ref "D247") (pin "2") (pinfunction "K_2") (pintype "passive"))
      (node (ref "D249") (pin "2") (pinfunction "K_2") (pintype "passive"))
      (node (ref "D251") (pin "2") (pinfunction "K_2") (pintype "passive"))
      (node (ref "D253") (pin "2") (pinfunction "K_2") (pintype "passive"))
      (node (ref "D267") (pin "2") (pinfunction "K_2") (pintype "passive"))
    )
    (net (code "15") (name "/row8") (class "Default")
      (node (ref "D244") (pin "2") (pinfunction "K_2") (pintype "passive"))
      (node (ref "D246") (pin "2") (pinfunction "K_2") (pintype "passive"))
      (node (ref "D248") (pin "2") (pinfunction "K_2") (pintype "passive"))
      (node (ref "D250") (pin "2") (pinfunction "K_2") (pintype "passive"))
      (node (ref "D252") (pin "2") (pinfunction "K_2") (pintype "passive"))
      (node (ref "D254") (pin "2") (pinfunction "K_2") (pintype "passive"))
      (node (ref "D256") (pin "2") (pinfunction "K_2") (pintype "passive"))
    )
    (net (code "16") (name "/row9") (class "Default")
      (node (ref "D257") (pin "2") (pinfunction "K_2") (pintype "passive"))
      (node (ref "D262") (pin "2") (pinfunction "K_2") (pintype "passive"))
      (node (ref "D264") (pin "2") (pinfunction "K_2") (pintype "passive"))
    )
    (net (code "17") (name "/row10") (class "Default")
      (node (ref "D255") (pin "2") (pinfunction "K_2") (pintype "passive"))
      (node (ref "D258") (pin "2") (pinfunction "K_2") (pintype "passive"))
      (node (ref "D259") (pin "2") (pinfunction "K_2") (pintype "passive"))
      (node (ref "D260") (pin "2") (pinfunction "K_2") (pintype "passive"))
      (node (ref "D261") (pin "2") (pinfunction "K_2") (pintype "passive"))
      (node (ref "D263") (pin "2") (pinfunction "K_2") (pintype "passive"))
    )
    (net (code "18") (name "Net-(D201-A)") (class "Default")
      (node (ref "D201") (pin "1") (pinfunction "A_1") (pintype "passive"))
      (node (ref "S201") (pin "1") (pinfunction "1_1") (pintype "passive"))
    )
    (net (code "19") (name "Net-(D202-A)") (class "Default")
      (node (ref "D202") (pin "1") (pinfunction "A_1") (pintype "passive"))
      (node (ref "S202") (pin "1") (pinfunction "1_1") (pintype "passive"))
    )
    (net (code "20") (name "Net-(D203-A)") (class "Default")
      (node (ref "D203") (pin "1") (pinfunction "A_1") (pintype "passive"))
      (node (ref "S203") (pin "1") (pinfunction "1_1") (pintype "passive"))
    )
    (net (code "21") (name "Net-(D204-A)") (class "Default")
      (node (ref "D204") (pin "1") (pinfunction "A_1") (pintype "passive"))
      (node (ref "S204") (pin "1") (pinfunction "1_1") (pintype "passive"))
    )
    (net (code "22") (name "Net-(D205-A)") (class "Default")
      (node (ref "D205") (pin "1") (pinfunction "A_1") (pintype "passive"))
      (node (ref "S205") (pin "1") (pinfunction "1_1") (pintype "passive"))
    )
    (net (code "23") (name "Net-(D206-A)") (class "Default")
      (node (ref "D206") (pin "1") (pinfunction "A_1") (pintype "passive"))
      (node (ref "S206") (pin "1") (pinfunction "1_1") (pintype "passive"))
    )
    (net (code "24") (name "Net-(D207-A)") (class "Default")
      (node (ref "D207") (pin "1") (pinfunction "A_1") (pintype "passive"))
      (node (ref "S207") (pin "1") (pinfunction "1_1") (pintype "passive"))
    )
    (net (code "25") (name "Net-(D208-A)") (class "Default")
      (node (ref "D208") (pin "1") (pinfunction "A_1") (pintype "passive"))
      (node (ref "S208") (pin "1") (pinfunction "1_1") (pintype "passive"))
    )
    (net (code "26") (name "Net-(D209-A)") (class "Default")
      (node (ref "D209") (pin "1") (pinfunction "A_1") (pintype "passive"))
      (node (ref "S209") (pin "1") (pinfunction "1_1") (pintype "passive"))
    )
    (net (code "27") (name "Net-(D210-A)") (class "Default")
      (node (ref "D210") (pin "1") (pinfunction "A_1") (pintype "passive"))
      (node (ref "S210") (pin "1") (pinfunction "1_1") (pintype "passive"))
    )
    (net (code "28") (name "Net-(D211-A)") (class "Default")
      (node (ref "D211") (pin "1") (pinfunction "A_1") (pintype "passive"))
      (node (ref "S211") (pin "1") (pinfunction "1_1") (pintype "passive"))
    )
    (net (code "29") (name "Net-(D212-A)") (class "Default")
      (node (ref "D212") (pin "1") (pinfunction "A_1") (pintype "passive"))
      (node (ref "S212") (pin "1") (pinfunction "1_1") (pintype "passive"))
    )
    (net (code "30") (name "Net-(D213-A)") (class "Default")
      (node (ref "D213") (pin "1") (pinfunction "A_1") (pintype "passive"))
      (node (ref "S213") (pin "1") (pinfunction "1_1") (pintype "passive"))
    )
    (net (code "31") (name "Net-(D214-A)") (class "Default")
      (node (ref "D214") (pin "1") (pinfunction "A_1") (pintype "passive"))
      (node (ref "S214") (pin "1") (pinfunction "1_1") (pintype "passive"))
    )
    (net (code "32") (name "Net-(D215-A)") (class "Default")
      (node (ref "D215") (pin "1") (pinfunction "A_1") (pintype "passive"))
      (node (ref "S215") (pin "2") (pinfunction "2_2") (pintype "passive"))
    )
    (net (code "33") (name "Net-(D216-A)") (class "Default")
      (node (ref "D216") (pin "1") (pinfunction "A_1") (pintype "passive"))
      (node (ref "S216") (pin "1") (pinfunction "1_1") (pintype "passive"))
    )
    (net (code "34") (name "Net-(D217-A)") (class "Default")
      (node (ref "D217") (pin "1") (pinfunction "A_1") (pintype "passive"))
      (node (ref "S217") (pin "1") (pinfunction "1_1") (pintype "passive"))
    )
    (net (code "35") (name "Net-(D218-A)") (class "Default")
      (node (ref "D218") (pin "1") (pinfunction "A_1") (pintype "passive"))
      (node (ref "S218") (pin "1") (pinfunction "1_1") (pintype "passive"))
    )
    (net (code "36") (name "Net-(D219-A)") (class "Default")
      (node (ref "D219") (pin "1") (pinfunction "A_1") (pintype "passive"))
      (node (ref "S219") (pin "1") (pinfunction "1_1") (pintype "passive"))
    )
    (net (code "37") (name "Net-(D220-A)") (class "Default")
      (node (ref "D220") (pin "1") (pinfunction "A_1") (pintype "passive"))
      (node (ref "S220") (pin "1") (pinfunction "1_1") (pintype "passive"))
    )
    (net (code "38") (name "Net-(D221-A)") (class "Default")
      (node (ref "D221") (pin "1") (pinfunction "A_1") (pintype "passive"))
      (node (ref "S221") (pin "1") (pinfunction "1_1") (pintype "passive"))
    )
    (net (code "39") (name "Net-(D222-A)") (class "Default")
      (node (ref "D222") (pin "1") (pinfunction "A_1") (pintype "passive"))
      (node (ref "S222") (pin "1") (pinfunction "1_1") (pintype "passive"))
    )
    (net (code "40") (name "Net-(D223-A)") (class "Default")
      (node (ref "D223") (pin "1") (pinfunction "A_1") (pintype "passive"))
      (node (ref "S223") (pin "1") (pinfunction "1_1") (pintype "passive"))
    )
    (net (code "41") (name "Net-(D224-A)") (class "Default")
      (node (ref "D224") (pin "1") (pinfunction "A_1") (pintype "passive"))
      (node (ref "S224") (pin "1") (pinfunction "1_1") (pintype "passive"))
    )
    (net (code "42") (name "Net-(D225-A)") (class "Default")
      (node (ref "D225") (pin "1") (pinfunction "A_1") (pintype "passive"))
      (node (ref "S225") (pin "1") (pinfunction "1_1") (pintype "passive"))
    )
    (net (code "43") (name "Net-(D226-A)") (class "Default")
      (node (ref "D226") (pin "1") (pinfunction "A_1") (pintype "passive"))
      (node (ref "S226") (pin "1") (pinfunction "1_1") (pintype "passive"))
    )
    (net (code "44") (name "Net-(D227-A)") (class "Default")
      (node (ref "D227") (pin "1") (pinfunction "A_1") (pintype "passive"))
      (node (ref "S227") (pin "1") (pinfunction "1_1") (pintype "passive"))
    )
    (net (code "45") (name "Net-(D228-A)") (class "Default")
      (node (ref "D228") (pin "1") (pinfunction "A_1") (pintype "passive"))
      (node (ref "S228") (pin "2") (pinfunction "2_2") (pintype "passive"))
    )
    (net (code "46") (name "Net-(D229-A)") (class "Default")
      (node (ref "D229") (pin "1") (pinfunction "A_1") (pintype "passive"))
      (node (ref "S229") (pin "1") (pinfunction "1_1") (pintype "passive"))
    )
    (net (code "47") (name "Net-(D230-A)") (class "Default")
      (node (ref "D230") (pin "1") (pinfunction "A_1") (pintype "passive"))
      (node (ref "S230") (pin "1") (pinfunction "1_1") (pintype "passive"))
    )
    (net (code "48") (name "Net-(D231-A)") (class "Default")
      (node (ref "D231") (pin "1") (pinfunction "A_1") (pintype "passive"))
      (node (ref "S231") (pin "1") (pinfunction "1_1") (pintype "passive"))
    )
    (net (code "49") (name "Net-(D232-A)") (class "Default")
      (node (ref "D232") (pin "1") (pinfunction "A_1") (pintype "passive"))
      (node (ref "S232") (pin "1") (pinfunction "1_1") (pintype "passive"))
    )
    (net (code "50") (name "Net-(D233-A)") (class "Default")
      (node (ref "D233") (pin "1") (pinfunction "A_1") (pintype "passive"))
      (node (ref "S233") (pin "1") (pinfunction "1_1") (pintype "passive"))
    )
    (net (code "51") (name "Net-(D234-A)") (class "Default")
      (node (ref "D234") (pin "1") (pinfunction "A_1") (pintype "passive"))
      (node (ref "S234") (pin "1") (pinfunction "1_1") (pintype "passive"))
    )
    (net (code "52") (name "Net-(D235-A)") (class "Default")
      (node (ref "D235") (pin "1") (pinfunction "A_1") (pintype "passive"))
      (node (ref "S235") (pin "1") (pinfunction "1_1") (pintype "passive"))
    )
    (net (code "53") (name "Net-(D236-A)") (class "Default")
      (node (ref "D236") (pin "1") (pinfunction "A_1") (pintype "passive"))
      (node (ref "S236") (pin "1") (pinfunction "1_1") (pintype "passive"))
    )
    (net (code "54") (name "Net-(D237-A)") (class "Default")
      (node (ref "D237") (pin "1") (pinfunction "A_1") (pintype "passive"))
      (node (ref "S237") (pin "1") (pinfunction "1_1") (pintype "passive"))
    )
    (net (code "55") (name "Net-(D238-A)") (class "Default")
      (node (ref "D238") (pin "1") (pinfunction "A_1") (pintype "passive"))
      (node (ref "S238") (pin "1") (pinfunction "1_1") (pintype "passive"))
    )
    (net (code "56") (name "Net-(D239-A)") (class "Default")
      (node (ref "D239") (pin "1") (pinfunction "A_1") (pintype "passive"))
      (node (ref "S239") (pin "1") (pinfunction "1_1") (pintype "passive"))
    )
    (net (code "57") (name "Net-(D240-A)") (class "Default")
      (node (ref "D240") (pin "1") (pinfunction "A_1") (pintype "passive"))
      (node (ref "S240") (pin "1") (pinfunction "1_1") (pintype "passive"))
    )
    (net (code "58") (name "Net-(D241-A)") (class "Default")
      (node (ref "D241") (pin "1") (pinfunction "A_1") (pintype "passive"))
      (node (ref "S241") (pin "1") (pinfunction "1_1") (pintype "passive"))
    )
    (net (code "59") (name "Net-(D242-A)") (class "Default")
      (node (ref "D242") (pin "1") (pinfunction "A_1") (pintype "passive"))
      (node (ref "S242") (pin "1") (pinfunction "1_1") (pintype "passive"))
    )
    (net (code "60") (name "Net-(D243-A)") (class "Default")
      (node (ref "D243") (pin "1") (pinfunction "A_1") (pintype "passive"))
      (node (ref "S243") (pin "1") (pinfunction "1_1") (pintype "passive"))
    )
    (net (code "61") (name "Net-(D244-A)") (class "Default")
      (node (ref "D244") (pin "1") (pinfunction "A_1") (pintype "passive"))
      (node (ref "S244") (pin "1") (pinfunction "1_1") (pintype "passive"))
    )
    (net (code "62") (name "Net-(D245-A)") (class "Default")
      (node (ref "D245") (pin "1") (pinfunction "A_1") (pintype "passive"))
      (node (ref "S245") (pin "1") (pinfunction "1_1") (pintype "passive"))
    )
    (net (code "63") (name "Net-(D246-A)") (class "Default")
      (node (ref "D246") (pin "1") (pinfunction "A_1") (pintype "passive"))
      (node (ref "S246") (pin "1") (pinfunction "1_1") (pintype "passive"))
    )
    (net (code "64") (name "Net-(D247-A)") (class "Default")
      (node (ref "D247") (pin "1") (pinfunction "A_1") (pintype "passive"))
      (node (ref "S247") (pin "1") (pinfunction "1_1") (pintype "passive"))
    )
    (net (code "65") (name "Net-(D248-A)") (class "Default")
      (node (ref "D248") (pin "1") (pinfunction "A_1") (pintype "passive"))
      (node (ref "S248") (pin "1") (pinfunction "1_1") (pintype "passive"))
    )
    (net (code "66") (name "Net-(D249-A)") (class "Default")
      (node (ref "D249") (pin "1") (pinfunction "A_1") (pintype "passive"))
      (node (ref "S249") (pin "1") (pinfunction "1_1") (pintype "passive"))
    )
    (net (code "67") (name "Net-(D250-A)") (class "Default")
      (node (ref "D250") (pin "1") (pinfunction "A_1") (pintype "passive"))
      (node (ref "S250") (pin "1") (pinfunction "1_1") (pintype "passive"))
    )
    (net (code "68") (name "Net-(D251-A)") (class "Default")
      (node (ref "D251") (pin "1") (pinfunction "A_1") (pintype "passive"))
      (node (ref "S251") (pin "1") (pinfunction "1_1") (pintype "passive"))
    )
    (net (code "69") (name "Net-(D252-A)") (class "Default")
      (node (ref "D252") (pin "1") (pinfunction "A_1") (pintype "passive"))
      (node (ref "S252") (pin "1") (pinfunction "1_1") (pintype "passive"))
    )
    (net (code "70") (name "Net-(D253-A)") (class "Default")
      (node (ref "D253") (pin "1") (pinfunction "A_1") (pintype "passive"))
      (node (ref "S253") (pin "1") (pinfunction "1_1") (pintype "passive"))
    )
    (net (code "71") (name "Net-(D254-A)") (class "Default")
      (node (ref "D254") (pin "1") (pinfunction "A_1") (pintype "passive"))
      (node (ref "S254") (pin "1") (pinfunction "1_1") (pintype "passive"))
    )
    (net (code "72") (name "Net-(D255-A)") (class "Default")
      (node (ref "D255") (pin "1") (pinfunction "A_1") (pintype "passive"))
      (node (ref "S255") (pin "1") (pinfunction "1_1") (pintype "passive"))
    )
    (net (code "73") (name "Net-(D256-A)") (class "Default")
      (node (ref "D256") (pin "1") (pinfunction "A_1") (pintype "passive"))
      (node (ref "S256") (pin "1") (pinfunction "1_1") (pintype "passive"))
    )
    (net (code "74") (name "Net-(D257-A)") (class "Default")
      (node (ref "D257") (pin "1") (pinfunction "A_1") (pintype "passive"))
      (node (ref "S257") (pin "2") (pinfunction "2_2") (pintype "passive"))
    )
    (net (code "75") (name "Net-(D258-A)") (class "Default")
      (node (ref "D258") (pin "1") (pinfunction "A_1") (pintype "passive"))
      (node (ref "S258") (pin "1") (pinfunction "1_1") (pintype "passive"))
    )
    (net (code "76") (name "Net-(D259-A)") (class "Default")
      (node (ref "D259") (pin "1") (pinfunction "A_1") (pintype "passive"))
      (node (ref "S259") (pin "2") (pinfunction "2_2") (pintype "passive"))
    )
    (net (code "77") (name "Net-(D260-A)") (class "Default")
      (node (ref "D260") (pin "1") (pinfunction "A_1") (pintype "passive"))
      (node (ref "S260") (pin "2") (pinfunction "2_2") (pintype "passive"))
    )
    (net (code "78") (name "Net-(D261-A)") (class "Default")
      (node (ref "D261") (pin "1") (pinfunction "A_1") (pintype "passive"))
      (node (ref "S261") (pin "1") (pinfunction "1_1") (pintype "passive"))
    )
    (net (code "79") (name "Net-(D262-A)") (class "Default")
      (node (ref "D262") (pin "1") (pinfunction "A_1") (pintype "passive"))
      (node (ref "S262") (pin "2") (pinfunction "2_2") (pintype "passive"))
    )
    (net (code "80") (name "Net-(D263-A)") (class "Default")
      (node (ref "D263") (pin "1") (pinfunction "A_1") (pintype "passive"))
      (node (ref "S263") (pin "2") (pinfunction "2_2") (pintype "passive"))
    )
    (net (code "81") (name "Net-(D264-A)") (class "Default")
      (node (ref "D264") (pin "1") (pinfunction "A_1") (pintype "passive"))
      (node (ref "S264") (pin "1") (pinfunction "1_1") (pintype "passive"))
    )
    (net (code "82") (name "Net-(D267-A)") (class "Default")
      (node (ref "D267") (pin "1") (pinfunction "A_1") (pintype "passive"))
      (node (ref "S267") (pin "1") (pinfunction "1_1") (pintype "passive"))
    )
  )
)
